# Digital_Inputs.net
KiCad netlist of a schematic drawn in Altium Designer
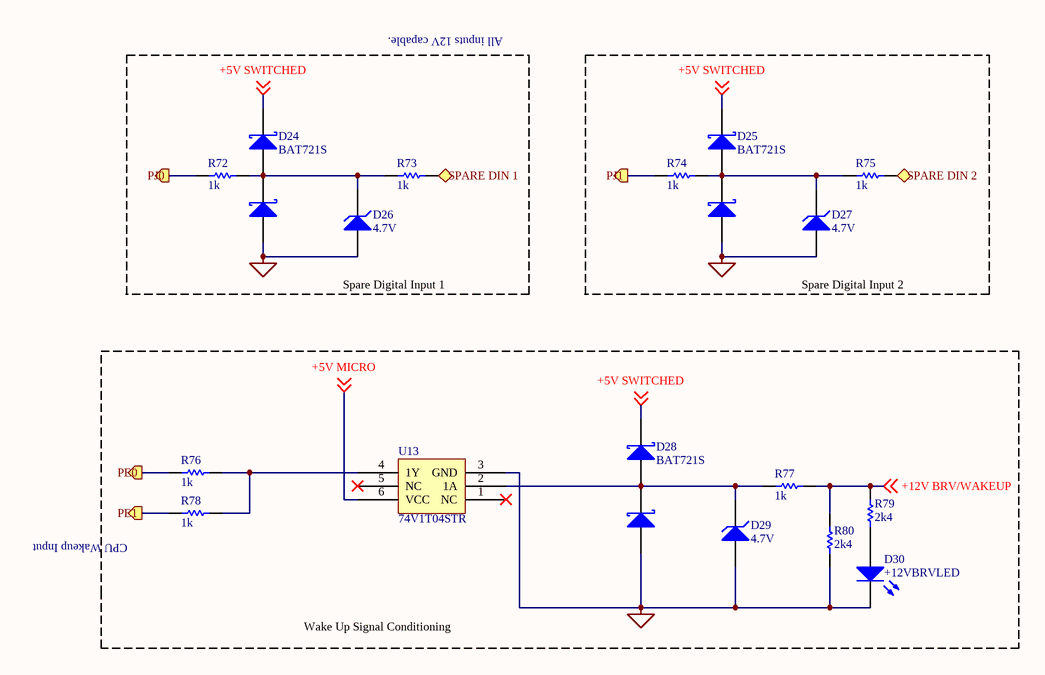
[diagram p0: Digital Inputs.SchDoc]

(export (version "E")
  (design (tool "Eeschema 10.0.6"))
  (components
    (comp (ref "D24")
      (value "BAT721S")
      (description "DUAL SCHOTTKY DIODE")
      (libsource (lib "FreeEMS Schematic Library") (part "BAT721S"))
    )
    (comp (ref "D25")
      (value "BAT721S")
      (description "DUAL SCHOTTKY DIODE")
      (libsource (lib "FreeEMS Schematic Library") (part "BAT721S"))
    )
    (comp (ref "D26")
      (value "4.7V")
      (footprint "DIODE-0.7")
      (description "Zener Diode")
      (fields (field (name "PUBLISHER") "Altium Limited"))
      (libsource (lib "Miscellaneous Devices") (part "D Zener"))
    )
    (comp (ref "D27")
      (value "4.7V")
      (footprint "DIODE-0.7")
      (description "Zener Diode")
      (fields (field (name "PUBLISHER") "Altium Limited"))
      (libsource (lib "Miscellaneous Devices") (part "D Zener"))
    )
    (comp (ref "D28")
      (value "BAT721S")
      (description "DUAL SCHOTTKY DIODE")
      (libsource (lib "FreeEMS Schematic Library") (part "BAT721S"))
    )
    (comp (ref "D29")
      (value "4.7V")
      (footprint "DIODE-0.7")
      (description "Zener Diode")
      (fields (field (name "PUBLISHER") "Altium Limited"))
      (libsource (lib "Miscellaneous Devices") (part "D Zener"))
    )
    (comp (ref "D30")
      (value "+12VBRVLED")
      (footprint "LED-0")
      (description "Typical INFRARED GaAs LED")
      (fields (field (name "PUBLISHER") "Altium Limited"))
      (libsource (lib "Miscellaneous Devices") (part "LED0"))
    )
    (comp (ref "R72")
      (value "1k")
      (footprint "AXIAL-0.3")
      (description "Resistor")
      (fields (field (name "PUBLISHER") "Altium Limited"))
      (libsource (lib "Miscellaneous Devices") (part "Res1"))
    )
    (comp (ref "R73")
      (value "1k")
      (footprint "AXIAL-0.3")
      (description "Resistor")
      (fields (field (name "PUBLISHER") "Altium Limited"))
      (libsource (lib "Miscellaneous Devices") (part "Res1"))
    )
    (comp (ref "R74")
      (value "1k")
      (footprint "AXIAL-0.3")
      (description "Resistor")
      (fields (field (name "PUBLISHER") "Altium Limited"))
      (libsource (lib "Miscellaneous Devices") (part "Res1"))
    )
    (comp (ref "R75")
      (value "1k")
      (footprint "AXIAL-0.3")
      (description "Resistor")
      (fields (field (name "PUBLISHER") "Altium Limited"))
      (libsource (lib "Miscellaneous Devices") (part "Res1"))
    )
    (comp (ref "R76")
      (value "1k")
      (footprint "AXIAL-0.3")
      (description "Resistor")
      (fields (field (name "PUBLISHER") "Altium Limited"))
      (libsource (lib "Miscellaneous Devices") (part "Res1"))
    )
    (comp (ref "R77")
      (value "1k")
      (footprint "AXIAL-0.3")
      (description "Resistor")
      (fields (field (name "PUBLISHER") "Altium Limited"))
      (libsource (lib "Miscellaneous Devices") (part "Res1"))
    )
    (comp (ref "R78")
      (value "1k")
      (footprint "AXIAL-0.3")
      (description "Resistor")
      (fields (field (name "PUBLISHER") "Altium Limited"))
      (libsource (lib "Miscellaneous Devices") (part "Res1"))
    )
    (comp (ref "R79")
      (value "2k4")
      (footprint "AXIAL-0.3")
      (description "Resistor")
      (fields (field (name "PUBLISHER") "Altium Limited"))
      (libsource (lib "Miscellaneous Devices") (part "Res1"))
    )
    (comp (ref "R80")
      (value "2k4")
      (footprint "AXIAL-0.3")
      (description "Resistor")
      (fields (field (name "PUBLISHER") "Altium Limited"))
      (libsource (lib "Miscellaneous Devices") (part "Res1"))
    )
    (comp (ref "U13") (value "74V1T04STR") (libsource (lib "FreeEMS Schematic Library") (part "74V1T04STR")))
  )
  (nets
    (net (code "1") (name "+5V MICRO") (class "Default")
      (node (ref "U13") (pin "6") (pinfunction "VCC_6") (pintype "passive"))
    )
    (net (code "2") (name "+5V SWITCHED") (class "Default")
      (node (ref "D24") (pin "2") (pinfunction "K_2") (pintype "passive"))
      (node (ref "D25") (pin "2") (pinfunction "K_2") (pintype "passive"))
      (node (ref "D28") (pin "2") (pinfunction "K_2") (pintype "passive"))
    )
    (net (code "3") (name "+12V BRV{slash}WAKEUP") (class "Default")
      (node (ref "R77") (pin "2") (pinfunction "2_2") (pintype "passive"))
      (node (ref "R79") (pin "2") (pinfunction "2_2") (pintype "passive"))
      (node (ref "R80") (pin "2") (pinfunction "2_2") (pintype "passive"))
    )
    (net (code "4") (name "/PE0") (class "Default")
      (node (ref "R76") (pin "2") (pinfunction "2_2") (pintype "passive"))
    )
    (net (code "5") (name "/PE1") (class "Default")
      (node (ref "R78") (pin "2") (pinfunction "2_2") (pintype "passive"))
    )
    (net (code "6") (name "/PJ0") (class "Default")
      (node (ref "R72") (pin "2") (pinfunction "2_2") (pintype "passive"))
    )
    (net (code "7") (name "/PJ1") (class "Default")
      (node (ref "R74") (pin "2") (pinfunction "2_2") (pintype "passive"))
    )
    (net (code "8") (name "/SPARE DIN 1") (class "Default")
      (node (ref "R73") (pin "2") (pinfunction "2_2") (pintype "passive"))
    )
    (net (code "9") (name "/SPARE DIN 2") (class "Default")
      (node (ref "R75") (pin "2") (pinfunction "2_2") (pintype "passive"))
    )
    (net (code "10") (name "<NO NET>") (class "Default")
      (node (ref "D24") (pin "1") (pinfunction "A_1") (pintype "passive"))
      (node (ref "D25") (pin "1") (pinfunction "A_1") (pintype "passive"))
      (node (ref "D26") (pin "1") (pinfunction "A_1") (pintype "passive"))
      (node (ref "D27") (pin "1") (pinfunction "A_1") (pintype "passive"))
      (node (ref "D28") (pin "1") (pinfunction "A_1") (pintype "passive"))
      (node (ref "D29") (pin "1") (pinfunction "A_1") (pintype "passive"))
      (node (ref "D30") (pin "2") (pinfunction "K_2") (pintype "passive"))
      (node (ref "R80") (pin "1") (pinfunction "1_1") (pintype "passive"))
      (node (ref "U13") (pin "3") (pinfunction "GND_3") (pintype "passive"))
    )
    (net (code "11") (name "Net-(D24-A2)") (class "Default")
      (node (ref "D24") (pin "3") (pinfunction "A2_3") (pintype "passive"))
      (node (ref "D26") (pin "2") (pinfunction "K_2") (pintype "passive"))
      (node (ref "R72") (pin "1") (pinfunction "1_1") (pintype "passive"))
      (node (ref "R73") (pin "1") (pinfunction "1_1") (pintype "passive"))
    )
    (net (code "12") (name "Net-(D25-A2)") (class "Default")
      (node (ref "D25") (pin "3") (pinfunction "A2_3") (pintype "passive"))
      (node (ref "D27") (pin "2") (pinfunction "K_2") (pintype "passive"))
      (node (ref "R74") (pin "1") (pinfunction "1_1") (pintype "passive"))
      (node (ref "R75") (pin "1") (pinfunction "1_1") (pintype "passive"))
    )
    (net (code "13") (name "Net-(D28-A2)") (class "Default")
      (node (ref "D28") (pin "3") (pinfunction "A2_3") (pintype "passive"))
      (node (ref "D29") (pin "2") (pinfunction "K_2") (pintype "passive"))
      (node (ref "R77") (pin "1") (pinfunction "1_1") (pintype "passive"))
      (node (ref "U13") (pin "2") (pinfunction "1A_2") (pintype "passive"))
    )
    (net (code "14") (name "Net-(D30-A)") (class "Default")
      (node (ref "D30") (pin "1") (pinfunction "A_1") (pintype "passive"))
      (node (ref "R79") (pin "1") (pinfunction "1_1") (pintype "passive"))
    )
    (net (code "15") (name "Net-(U13-1Y)") (class "Default")
      (node (ref "R76") (pin "1") (pinfunction "1_1") (pintype "passive"))
      (node (ref "R78") (pin "1") (pinfunction "1_1") (pintype "passive"))
      (node (ref "U13") (pin "4") (pinfunction "1Y_4") (pintype "passive"))
    )
    (net (code "16") (name "unconnected-(U13-NC-Pad1)") (class "Default")
      (node (ref "U13") (pin "1") (pinfunction "NC_1") (pintype "passive+no_connect"))
    )
    (net (code "17") (name "unconnected-(U13-NC-Pad5)") (class "Default")
      (node (ref "U13") (pin "5") (pinfunction "NC_5") (pintype "passive+no_connect"))
    )
  )
)
